# main.net
KiCad netlist of a schematic drawn in EAGLE
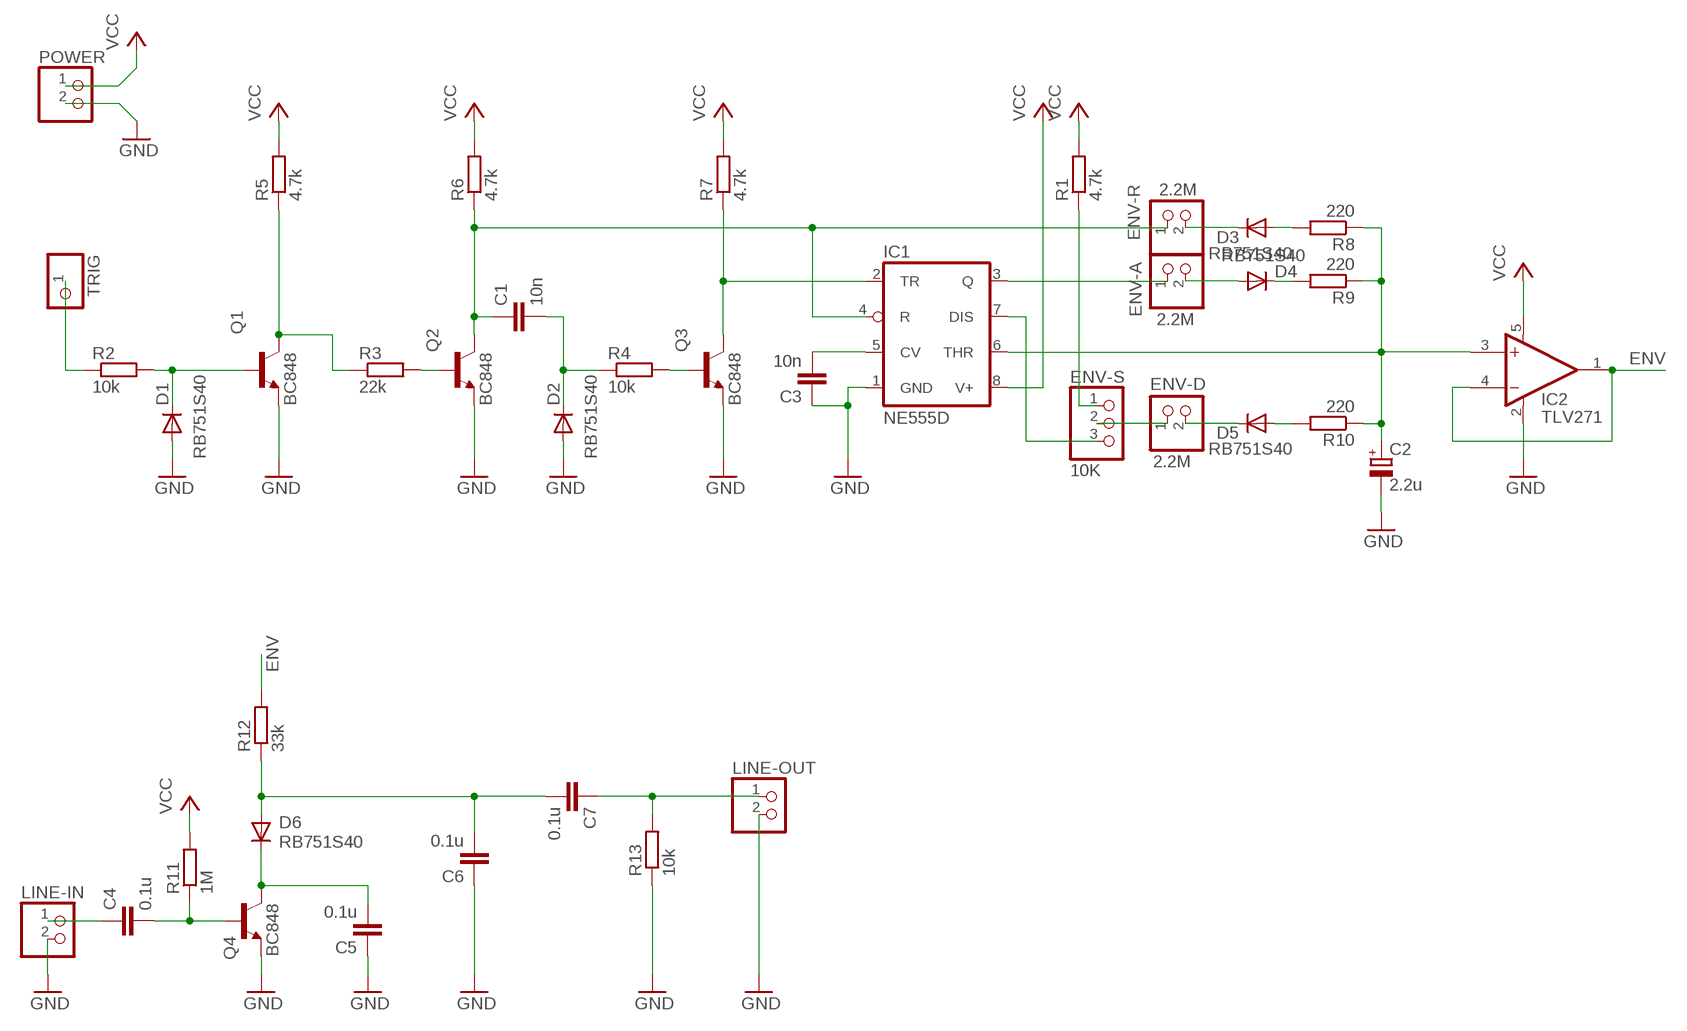
[diagram p0: schematic, sheet 1]

(export (version "E")
  (design (tool "Eeschema 10.0.6"))
  (components
    (comp (ref "C1")
      (value "10n")
      (footprint "eagle-import:C0805")
      (libsource (lib "eagle-import") (part "C-EUC0805"))
    )
    (comp (ref "C2")
      (value "2.2u")
      (footprint "eagle-import:PANASONIC_A")
      (libsource (lib "eagle-import") (part "CPOL-EUA"))
    )
    (comp (ref "C3")
      (value "10n")
      (footprint "eagle-import:C0805")
      (libsource (lib "eagle-import") (part "C-EUC0805"))
    )
    (comp (ref "C4")
      (value "0.1u")
      (footprint "eagle-import:C0805")
      (libsource (lib "eagle-import") (part "C-EUC0805"))
    )
    (comp (ref "C5")
      (value "0.1u")
      (footprint "eagle-import:C0805")
      (libsource (lib "eagle-import") (part "C-EUC0805"))
    )
    (comp (ref "C6")
      (value "0.1u")
      (footprint "eagle-import:C0805")
      (libsource (lib "eagle-import") (part "C-EUC0805"))
    )
    (comp (ref "C7")
      (value "0.1u")
      (footprint "eagle-import:C0805")
      (libsource (lib "eagle-import") (part "C-EUC0805"))
    )
    (comp (ref "D1")
      (value "RB751S40")
      (footprint "eagle-import:SOD523")
      (libsource (lib "eagle-import") (part "DIODE-SOD523"))
    )
    (comp (ref "D2")
      (value "RB751S40")
      (footprint "eagle-import:SOD523")
      (libsource (lib "eagle-import") (part "DIODE-SOD523"))
    )
    (comp (ref "D3")
      (value "RB751S40")
      (footprint "eagle-import:SOD523")
      (libsource (lib "eagle-import") (part "DIODE-SOD523"))
    )
    (comp (ref "D4")
      (value "RB751S40")
      (footprint "eagle-import:SOD523")
      (libsource (lib "eagle-import") (part "DIODE-SOD523"))
    )
    (comp (ref "D5")
      (value "RB751S40")
      (footprint "eagle-import:SOD523")
      (libsource (lib "eagle-import") (part "DIODE-SOD523"))
    )
    (comp (ref "D6")
      (value "RB751S40")
      (footprint "eagle-import:SOD523")
      (libsource (lib "eagle-import") (part "DIODE-SOD523"))
    )
    (comp (ref "ENV-A")
      (value "2.2M")
      (footprint "eagle-import:1X02M")
      (libsource (lib "eagle-import") (part "PINHD-1X02_2.00"))
    )
    (comp (ref "ENV-D")
      (value "2.2M")
      (footprint "eagle-import:1X02M")
      (libsource (lib "eagle-import") (part "PINHD-1X02_2.00"))
    )
    (comp (ref "ENV-R")
      (value "2.2M")
      (footprint "eagle-import:1X02M")
      (libsource (lib "eagle-import") (part "PINHD-1X02_2.00"))
    )
    (comp (ref "ENV-S")
      (value "10K")
      (footprint "eagle-import:1X03M")
      (libsource (lib "eagle-import") (part "PINHD-1X03_2.00"))
    )
    (comp (ref "IC1")
      (value "NE555D")
      (footprint "eagle-import:SO08")
      (libsource (lib "eagle-import") (part "555DNE"))
    )
    (comp (ref "IC2")
      (value "TLV271")
      (footprint "eagle-import:SOT23-5")
      (libsource (lib "eagle-import") (part "TLV271-OP-AMP"))
    )
    (comp (ref "LINE-IN")
      (value "PINHD-1X02_2.00")
      (footprint "eagle-import:1X02M")
      (libsource (lib "eagle-import") (part "PINHD-1X02_2.00"))
    )
    (comp (ref "LINE-OUT")
      (value "PINHD-1X02_2.00")
      (footprint "eagle-import:1X02M")
      (libsource (lib "eagle-import") (part "PINHD-1X02_2.00"))
    )
    (comp (ref "POWER")
      (value "PINHD-1X02_2.00")
      (footprint "eagle-import:1X02M")
      (libsource (lib "eagle-import") (part "PINHD-1X02_2.00"))
    )
    (comp (ref "Q1")
      (value "BC848")
      (footprint "eagle-import:SOT23")
      (libsource (lib "eagle-import") (part "BC848SMDCLT1"))
    )
    (comp (ref "Q2")
      (value "BC848")
      (footprint "eagle-import:SOT23")
      (libsource (lib "eagle-import") (part "BC848SMDCLT1"))
    )
    (comp (ref "Q3")
      (value "BC848")
      (footprint "eagle-import:SOT23")
      (libsource (lib "eagle-import") (part "BC848SMDCLT1"))
    )
    (comp (ref "Q4")
      (value "BC848")
      (footprint "eagle-import:SOT23")
      (libsource (lib "eagle-import") (part "BC848SMDCLT1"))
    )
    (comp (ref "R1")
      (value "4.7k")
      (footprint "eagle-import:R0805W")
      (libsource (lib "eagle-import") (part "R-EU_R0805W"))
    )
    (comp (ref "R2")
      (value "10k")
      (footprint "eagle-import:R0805W")
      (libsource (lib "eagle-import") (part "R-EU_R0805W"))
    )
    (comp (ref "R3")
      (value "22k")
      (footprint "eagle-import:R0805W")
      (libsource (lib "eagle-import") (part "R-EU_R0805W"))
    )
    (comp (ref "R4")
      (value "10k")
      (footprint "eagle-import:R0805W")
      (libsource (lib "eagle-import") (part "R-EU_R0805W"))
    )
    (comp (ref "R5")
      (value "4.7k")
      (footprint "eagle-import:R0805W")
      (libsource (lib "eagle-import") (part "R-EU_R0805W"))
    )
    (comp (ref "R6")
      (value "4.7k")
      (footprint "eagle-import:R0805W")
      (libsource (lib "eagle-import") (part "R-EU_R0805W"))
    )
    (comp (ref "R7")
      (value "4.7k")
      (footprint "eagle-import:R0805W")
      (libsource (lib "eagle-import") (part "R-EU_R0805W"))
    )
    (comp (ref "R8")
      (value "220")
      (footprint "eagle-import:R0805W")
      (libsource (lib "eagle-import") (part "R-EU_R0805W"))
    )
    (comp (ref "R9")
      (value "220")
      (footprint "eagle-import:R0805W")
      (libsource (lib "eagle-import") (part "R-EU_R0805W"))
    )
    (comp (ref "R10")
      (value "220")
      (footprint "eagle-import:R0805W")
      (libsource (lib "eagle-import") (part "R-EU_R0805W"))
    )
    (comp (ref "R11")
      (value "1M")
      (footprint "eagle-import:R0805W")
      (libsource (lib "eagle-import") (part "R-EU_R0805W"))
    )
    (comp (ref "R12")
      (value "33k")
      (footprint "eagle-import:R0805W")
      (libsource (lib "eagle-import") (part "R-EU_R0805W"))
    )
    (comp (ref "R13")
      (value "10k")
      (footprint "eagle-import:R0805W")
      (libsource (lib "eagle-import") (part "R-EU_R0805W"))
    )
    (comp (ref "TRIG")
      (value "PINHD-1X01_2.00")
      (footprint "eagle-import:1X01M")
      (libsource (lib "eagle-import") (part "PINHD-1X01_2.00"))
    )
  )
  (nets
    (net (code "1") (name "/ENV") (class "Default")
      (node (ref "IC2") (pin "1") (pinfunction "OUT_1") (pintype "output"))
      (node (ref "IC2") (pin "4") (pinfunction "-IN_4") (pintype "input"))
      (node (ref "R12") (pin "2") (pinfunction "2_2") (pintype "passive"))
    )
    (net (code "2") (name "GND") (class "Default")
      (node (ref "C2") (pin "-") (pinfunction "-_-") (pintype "passive"))
      (node (ref "C3") (pin "1") (pinfunction "1_1") (pintype "passive"))
      (node (ref "C5") (pin "1") (pinfunction "1_1") (pintype "passive"))
      (node (ref "C6") (pin "1") (pinfunction "1_1") (pintype "passive"))
      (node (ref "D1") (pin "A") (pinfunction "A_A") (pintype "passive"))
      (node (ref "D2") (pin "A") (pinfunction "A_A") (pintype "passive"))
      (node (ref "IC1") (pin "1") (pinfunction "GND_1") (pintype "power_in"))
      (node (ref "IC2") (pin "2") (pinfunction "V-_2") (pintype "power_in"))
      (node (ref "LINE-IN") (pin "2") (pinfunction "2_2") (pintype "passive"))
      (node (ref "LINE-OUT") (pin "2") (pinfunction "2_2") (pintype "passive"))
      (node (ref "POWER") (pin "2") (pinfunction "2_2") (pintype "passive"))
      (node (ref "Q1") (pin "2") (pinfunction "E_2") (pintype "passive"))
      (node (ref "Q2") (pin "2") (pinfunction "E_2") (pintype "passive"))
      (node (ref "Q3") (pin "2") (pinfunction "E_2") (pintype "passive"))
      (node (ref "Q4") (pin "2") (pinfunction "E_2") (pintype "passive"))
      (node (ref "R13") (pin "1") (pinfunction "1_1") (pintype "passive"))
    )
    (net (code "3") (name "Net-(C1-Pad2)") (class "Default")
      (node (ref "C1") (pin "2") (pinfunction "2_2") (pintype "passive"))
      (node (ref "D2") (pin "C") (pinfunction "C_C") (pintype "passive"))
      (node (ref "R4") (pin "1") (pinfunction "1_1") (pintype "passive"))
    )
    (net (code "4") (name "Net-(C4-Pad1)") (class "Default")
      (node (ref "C4") (pin "1") (pinfunction "1_1") (pintype "passive"))
      (node (ref "LINE-IN") (pin "1") (pinfunction "1_1") (pintype "passive"))
    )
    (net (code "5") (name "Net-(C6-Pad2)") (class "Default")
      (node (ref "C6") (pin "2") (pinfunction "2_2") (pintype "passive"))
      (node (ref "C7") (pin "2") (pinfunction "2_2") (pintype "passive"))
      (node (ref "D6") (pin "A") (pinfunction "A_A") (pintype "passive"))
      (node (ref "R12") (pin "1") (pinfunction "1_1") (pintype "passive"))
    )
    (net (code "6") (name "Net-(C7-Pad1)") (class "Default")
      (node (ref "C7") (pin "1") (pinfunction "1_1") (pintype "passive"))
      (node (ref "LINE-OUT") (pin "1") (pinfunction "1_1") (pintype "passive"))
      (node (ref "R13") (pin "2") (pinfunction "2_2") (pintype "passive"))
    )
    (net (code "7") (name "Net-(D3-PadA)") (class "Default")
      (node (ref "D3") (pin "A") (pinfunction "A_A") (pintype "passive"))
      (node (ref "R8") (pin "2") (pinfunction "2_2") (pintype "passive"))
    )
    (net (code "8") (name "Net-(D3-PadC)") (class "Default")
      (node (ref "D3") (pin "C") (pinfunction "C_C") (pintype "passive"))
      (node (ref "ENV-R") (pin "2") (pinfunction "2_2") (pintype "passive"))
    )
    (net (code "9") (name "Net-(D4-PadA)") (class "Default")
      (node (ref "D4") (pin "A") (pinfunction "A_A") (pintype "passive"))
      (node (ref "ENV-A") (pin "2") (pinfunction "2_2") (pintype "passive"))
    )
    (net (code "10") (name "Net-(D4-PadC)") (class "Default")
      (node (ref "D4") (pin "C") (pinfunction "C_C") (pintype "passive"))
      (node (ref "R9") (pin "2") (pinfunction "2_2") (pintype "passive"))
    )
    (net (code "11") (name "Net-(D5-PadA)") (class "Default")
      (node (ref "D5") (pin "A") (pinfunction "A_A") (pintype "passive"))
      (node (ref "R10") (pin "2") (pinfunction "2_2") (pintype "passive"))
    )
    (net (code "12") (name "Net-(D5-PadC)") (class "Default")
      (node (ref "D5") (pin "C") (pinfunction "C_C") (pintype "passive"))
      (node (ref "ENV-D") (pin "2") (pinfunction "2_2") (pintype "passive"))
    )
    (net (code "13") (name "Net-(ENV-D-Pad1)") (class "Default")
      (node (ref "ENV-D") (pin "1") (pinfunction "1_1") (pintype "passive"))
      (node (ref "ENV-S") (pin "2") (pinfunction "2_2") (pintype "passive"))
    )
    (net (code "14") (name "Net-(ENV-S-Pad1)") (class "Default")
      (node (ref "ENV-S") (pin "1") (pinfunction "1_1") (pintype "passive"))
      (node (ref "R1") (pin "1") (pinfunction "1_1") (pintype "passive"))
    )
    (net (code "15") (name "Net-(IC1-CV)") (class "Default")
      (node (ref "C3") (pin "2") (pinfunction "2_2") (pintype "passive"))
      (node (ref "IC1") (pin "5") (pinfunction "CV_5") (pintype "input"))
    )
    (net (code "16") (name "Net-(IC1-DIS)") (class "Default")
      (node (ref "ENV-S") (pin "3") (pinfunction "3_3") (pintype "passive"))
      (node (ref "IC1") (pin "7") (pinfunction "DIS_7") (pintype "input"))
    )
    (net (code "17") (name "Net-(IC1-Q)") (class "Default")
      (node (ref "ENV-A") (pin "1") (pinfunction "1_1") (pintype "passive"))
      (node (ref "IC1") (pin "3") (pinfunction "Q_3") (pintype "output"))
    )
    (net (code "18") (name "Net-(IC1-R)") (class "Default")
      (node (ref "C1") (pin "1") (pinfunction "1_1") (pintype "passive"))
      (node (ref "ENV-R") (pin "1") (pinfunction "1_1") (pintype "passive"))
      (node (ref "IC1") (pin "4") (pinfunction "R_4") (pintype "input"))
      (node (ref "Q2") (pin "3") (pinfunction "C_3") (pintype "passive"))
      (node (ref "R6") (pin "1") (pinfunction "1_1") (pintype "passive"))
    )
    (net (code "19") (name "Net-(IC1-THR)") (class "Default")
      (node (ref "C2") (pin "+") (pinfunction "+_+") (pintype "passive"))
      (node (ref "IC1") (pin "6") (pinfunction "THR_6") (pintype "input"))
      (node (ref "IC2") (pin "3") (pinfunction "+IN_3") (pintype "input"))
      (node (ref "R10") (pin "1") (pinfunction "1_1") (pintype "passive"))
      (node (ref "R8") (pin "1") (pinfunction "1_1") (pintype "passive"))
      (node (ref "R9") (pin "1") (pinfunction "1_1") (pintype "passive"))
    )
    (net (code "20") (name "Net-(IC1-TR)") (class "Default")
      (node (ref "IC1") (pin "2") (pinfunction "TR_2") (pintype "input"))
      (node (ref "Q3") (pin "3") (pinfunction "C_3") (pintype "passive"))
      (node (ref "R7") (pin "1") (pinfunction "1_1") (pintype "passive"))
    )
    (net (code "21") (name "Net-(Q1-B)") (class "Default")
      (node (ref "D1") (pin "C") (pinfunction "C_C") (pintype "passive"))
      (node (ref "Q1") (pin "1") (pinfunction "B_1") (pintype "passive"))
      (node (ref "R2") (pin "2") (pinfunction "2_2") (pintype "passive"))
    )
    (net (code "22") (name "Net-(Q1-C)") (class "Default")
      (node (ref "Q1") (pin "3") (pinfunction "C_3") (pintype "passive"))
      (node (ref "R3") (pin "1") (pinfunction "1_1") (pintype "passive"))
      (node (ref "R5") (pin "1") (pinfunction "1_1") (pintype "passive"))
    )
    (net (code "23") (name "Net-(Q2-B)") (class "Default")
      (node (ref "Q2") (pin "1") (pinfunction "B_1") (pintype "passive"))
      (node (ref "R3") (pin "2") (pinfunction "2_2") (pintype "passive"))
    )
    (net (code "24") (name "Net-(Q3-B)") (class "Default")
      (node (ref "Q3") (pin "1") (pinfunction "B_1") (pintype "passive"))
      (node (ref "R4") (pin "2") (pinfunction "2_2") (pintype "passive"))
    )
    (net (code "25") (name "Net-(Q4-B)") (class "Default")
      (node (ref "C4") (pin "2") (pinfunction "2_2") (pintype "passive"))
      (node (ref "Q4") (pin "1") (pinfunction "B_1") (pintype "passive"))
      (node (ref "R11") (pin "1") (pinfunction "1_1") (pintype "passive"))
    )
    (net (code "26") (name "Net-(Q4-C)") (class "Default")
      (node (ref "C5") (pin "2") (pinfunction "2_2") (pintype "passive"))
      (node (ref "D6") (pin "C") (pinfunction "C_C") (pintype "passive"))
      (node (ref "Q4") (pin "3") (pinfunction "C_3") (pintype "passive"))
    )
    (net (code "27") (name "Net-(R2-Pad1)") (class "Default")
      (node (ref "R2") (pin "1") (pinfunction "1_1") (pintype "passive"))
      (node (ref "TRIG") (pin "1") (pinfunction "1_1") (pintype "passive"))
    )
    (net (code "28") (name "VCC") (class "Default")
      (node (ref "IC1") (pin "8") (pinfunction "V+_8") (pintype "power_in"))
      (node (ref "IC2") (pin "5") (pinfunction "V+_5") (pintype "power_in"))
      (node (ref "POWER") (pin "1") (pinfunction "1_1") (pintype "passive"))
      (node (ref "R1") (pin "2") (pinfunction "2_2") (pintype "passive"))
      (node (ref "R11") (pin "2") (pinfunction "2_2") (pintype "passive"))
      (node (ref "R5") (pin "2") (pinfunction "2_2") (pintype "passive"))
      (node (ref "R6") (pin "2") (pinfunction "2_2") (pintype "passive"))
      (node (ref "R7") (pin "2") (pinfunction "2_2") (pintype "passive"))
    )
  )
)
